# MCU.net
KiCad netlist of a schematic drawn in Altium Designer
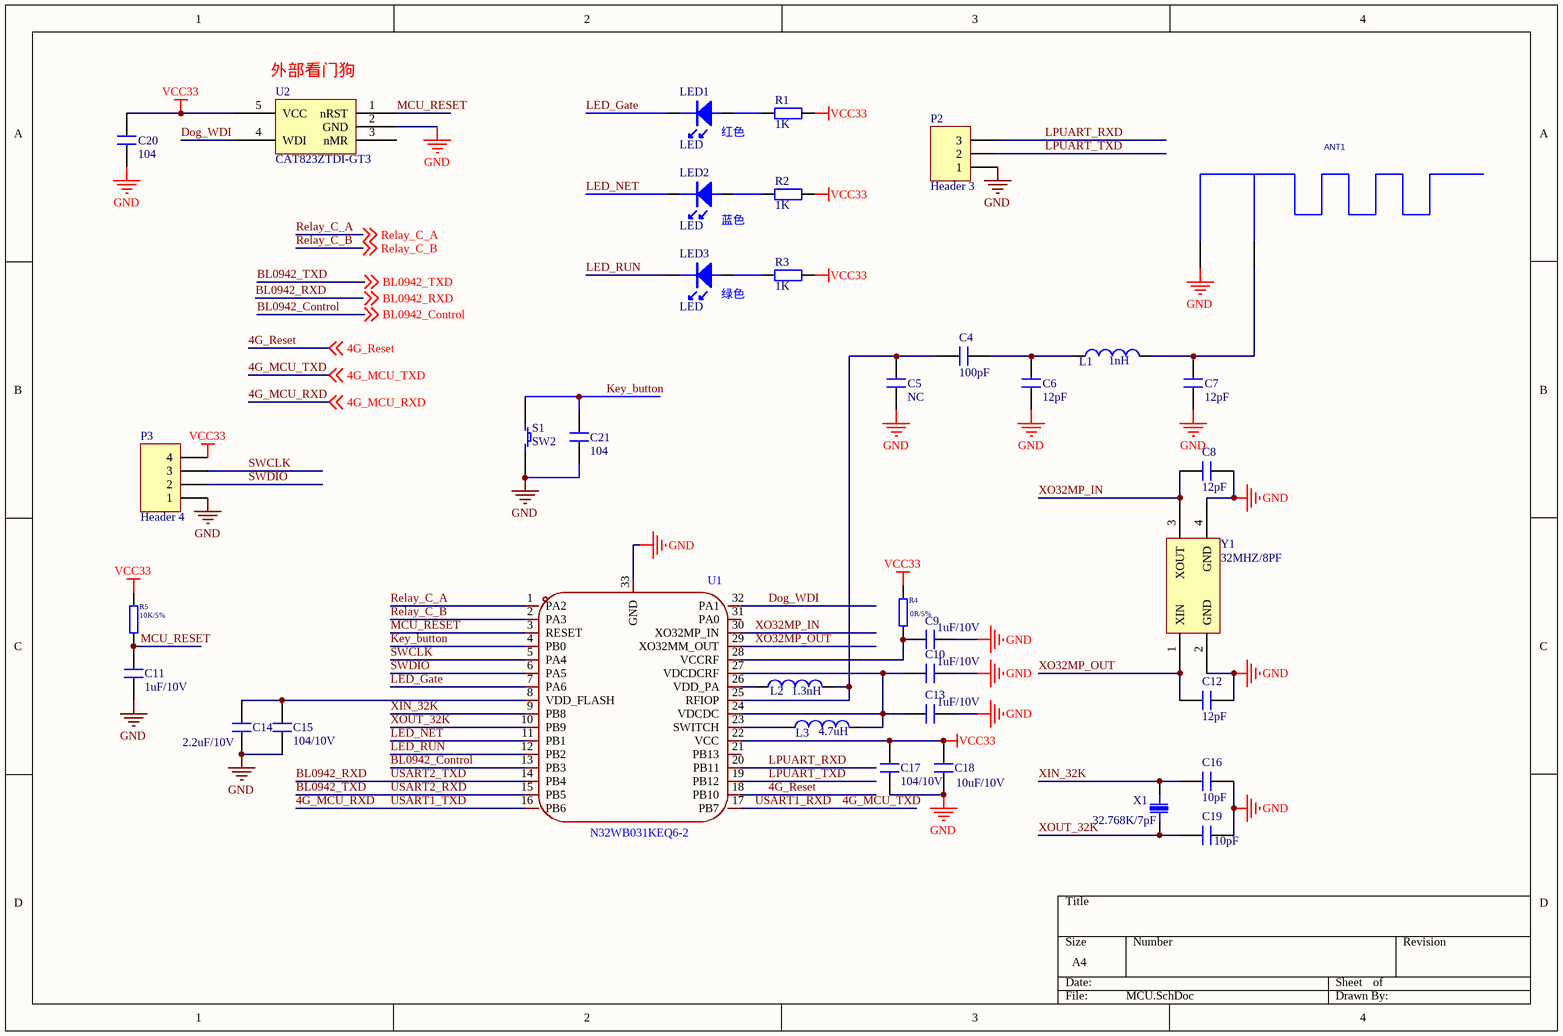
[diagram p0: MCU.SchDoc]

(export (version "E")
  (design (tool "Eeschema 10.0.6"))
  (components
    (comp (ref "ANT1")
      (value "ANT_2.4G")
      (footprint "ANTENNA_IIFA_BLE_MIRROR")
      (description "连接器，4PIN，2.0mm脚间距离，防呆直插件")
      (libsource (lib "*") (part "ANT_2.4G"))
    )
    (comp (ref "C4") (value "100pF") (footprint "0603R") (libsource (lib "ES_Schematic") (part "CAP_1")))
    (comp (ref "C5") (value "NC") (footprint "0603R") (libsource (lib "ES_Schematic") (part "CAP_1")))
    (comp (ref "C6") (value "12pF") (footprint "0603R") (libsource (lib "ES_Schematic") (part "CAP_1")))
    (comp (ref "C7") (value "12pF") (footprint "0603R") (libsource (lib "ES_Schematic") (part "CAP_1")))
    (comp (ref "C8") (value "12pF") (footprint "0603r") (libsource (lib "ES_Schematic") (part "CAP")))
    (comp (ref "C9") (value "1uF/10V") (footprint "0603R") (libsource (lib "ES_Schematic") (part "CAP_1")))
    (comp (ref "C10") (value "1uF/10V") (footprint "0603R") (libsource (lib "ES_Schematic") (part "CAP_1")))
    (comp (ref "C11") (value "1uF/10V") (footprint "0603R") (libsource (lib "ES_Schematic") (part "CAP_1")))
    (comp (ref "C12") (value "12pF") (footprint "0603r") (libsource (lib "ES_Schematic") (part "CAP")))
    (comp (ref "C13") (value "1uF/10V") (footprint "0603R") (libsource (lib "ES_Schematic") (part "CAP_1")))
    (comp (ref "C14") (value "2.2uF/10V") (footprint "0603R") (libsource (lib "ES_Schematic") (part "CAP_1")))
    (comp (ref "C15") (value "104/10V") (footprint "0603R") (libsource (lib "ES_Schematic") (part "CAP_1")))
    (comp (ref "C16") (value "10pF") (footprint "0603r") (libsource (lib "ES_Schematic") (part "CAP")))
    (comp (ref "C17") (value "104/10V") (footprint "0603R") (libsource (lib "ES_Schematic") (part "CAP_1")))
    (comp (ref "C18") (value "10uF/10V") (footprint "0603R") (libsource (lib "ES_Schematic") (part "CAP_1")))
    (comp (ref "C19") (value "10pF") (footprint "0603r") (libsource (lib "ES_Schematic") (part "CAP")))
    (comp (ref "C20") (value "104") (footprint "0603R") (libsource (lib "ES_Schematic") (part "CAP")))
    (comp (ref "C21") (value "104") (footprint "0603R") (libsource (lib "ES_Schematic") (part "CAP")))
    (comp (ref "L1")
      (value "1nH")
      (footprint "贴片电感5020")
      (description "Inductor")
      (fields (field (name "PUBLISHER") "Altium Limited"))
      (libsource (lib "Miscellaneous Devices") (part "Inductor"))
    )
    (comp (ref "L2")
      (value "1.3nH")
      (footprint "贴片电感5020")
      (description "Inductor")
      (fields (field (name "PUBLISHER") "Altium Limited"))
      (libsource (lib "Miscellaneous Devices") (part "Inductor"))
    )
    (comp (ref "L3")
      (value "4.7uH")
      (footprint "贴片电感5020")
      (description "Inductor")
      (fields (field (name "PUBLISHER") "Altium Limited"))
      (libsource (lib "Miscellaneous Devices") (part "Inductor"))
    )
    (comp (ref "LED1") (value "LED") (footprint "LED0805") (libsource (lib "ES_Schematic") (part "LED")))
    (comp (ref "LED2") (value "LED") (footprint "LED0805") (libsource (lib "ES_Schematic") (part "LED")))
    (comp (ref "LED3") (value "LED") (footprint "LED0805") (libsource (lib "ES_Schematic") (part "LED")))
    (comp (ref "P2")
      (value "Header 3")
      (footprint "HDR1X3")
      (description "Header, 3-Pin")
      (fields (field (name "PUBLISHER") "Altium Limited"))
      (libsource (lib "Miscellaneous Connectors") (part "Header 3"))
    )
    (comp (ref "P3")
      (value "Header 4")
      (footprint "HDR1X4")
      (description "Header, 4-Pin")
      (fields (field (name "PUBLISHER") "Altium Limited"))
      (libsource (lib "Miscellaneous Connectors") (part "Header 4"))
    )
    (comp (ref "R1")
      (value "1K")
      (footprint "0603R")
      (fields (field (name "Comment") "Res2") (field (name "PUBLISHER") "Altium Limited"))
      (libsource (lib "Miscellaneous Devices") (part "Res2"))
    )
    (comp (ref "R2")
      (value "1K")
      (footprint "0603R")
      (fields (field (name "Comment") "Res2") (field (name "PUBLISHER") "Altium Limited"))
      (libsource (lib "Miscellaneous Devices") (part "Res2"))
    )
    (comp (ref "R3")
      (value "1K")
      (footprint "0603R")
      (fields (field (name "Comment") "Res2") (field (name "PUBLISHER") "Altium Limited"))
      (libsource (lib "Miscellaneous Devices") (part "Res2"))
    )
    (comp (ref "R4") (value "0R/5%") (footprint "0603R") (libsource (lib "ES_Schematic") (part "RES")))
    (comp (ref "R5") (value "10K/5%") (footprint "0603R") (libsource (lib "ES_Schematic") (part "RES")))
    (comp (ref "S1")
      (value "SW2")
      (footprint "4.5*4.5贴片4脚独立按键")
      (libsource (lib "ES_Schematic") (part "SW2"))
    )
    (comp (ref "U1")
      (value "N32WB031KEQ6-2")
      (footprint "QFN-32_L4.0-W4.0-P0.40-TL-EP2.8")
      (fields (field (name "MANUFACTURER") "Nations(国民技术)"))
      (libsource (lib "altium-import") (part "root_0_N32WB031KEQ6-2_"))
    )
    (comp (ref "U2")
      (value "CAT823ZTDI-GT3")
      (footprint "SOT-23-5")
      (libsource (lib "ES_Schematic") (part "CAT823"))
    )
    (comp (ref "X1") (value "32.768K/7pF") (footprint "Y3215") (libsource (lib "ES_Schematic") (part "XTAL")))
    (comp (ref "Y1") (value "32MHZ/8PF") (footprint "3225") (libsource (lib "others") (part "12MHz无源")))
  )
  (nets
    (net (code "1") (name "/Dog_WDI") (class "Default")
      (node (ref "U1") (pin "32") (pinfunction "PA1_32") (pintype "passive"))
      (node (ref "U2") (pin "4") (pinfunction "WDI_4") (pintype "passive"))
    )
    (net (code "2") (name "/Key_button") (class "Default")
      (node (ref "C21") (pin "1") (pinfunction "1_1") (pintype "passive"))
      (node (ref "S1") (pin "1") (pinfunction "1_1") (pintype "passive"))
      (node (ref "U1") (pin "4") (pinfunction "PB0_4") (pintype "passive"))
    )
    (net (code "3") (name "/LED_Gate") (class "Default")
      (node (ref "LED1") (pin "2") (pinfunction "2_2") (pintype "passive"))
      (node (ref "U1") (pin "7") (pinfunction "PA6_7") (pintype "passive"))
    )
    (net (code "4") (name "/LED_NET") (class "Default")
      (node (ref "LED2") (pin "2") (pinfunction "2_2") (pintype "passive"))
      (node (ref "U1") (pin "11") (pinfunction "PB1_11") (pintype "passive"))
    )
    (net (code "5") (name "/LED_RUN") (class "Default")
      (node (ref "LED3") (pin "2") (pinfunction "2_2") (pintype "passive"))
      (node (ref "U1") (pin "12") (pinfunction "PB2_12") (pintype "passive"))
    )
    (net (code "6") (name "/LPUART_RXD") (class "Default")
      (node (ref "P2") (pin "3") (pinfunction "3_3") (pintype "passive"))
      (node (ref "U1") (pin "20") (pinfunction "PB11_20") (pintype "passive"))
    )
    (net (code "7") (name "/LPUART_TXD") (class "Default")
      (node (ref "P2") (pin "2") (pinfunction "2_2") (pintype "passive"))
      (node (ref "U1") (pin "19") (pinfunction "PB12_19") (pintype "passive"))
    )
    (net (code "8") (name "/MCU_RESET") (class "Default")
      (node (ref "C11") (pin "2") (pinfunction "2_2") (pintype "passive"))
      (node (ref "R5") (pin "2") (pinfunction "2_2") (pintype "passive"))
      (node (ref "U1") (pin "3") (pinfunction "RESET_3") (pintype "passive"))
      (node (ref "U2") (pin "1") (pinfunction "nRST_1") (pintype "passive"))
    )
    (net (code "9") (name "/SWCLK") (class "Default")
      (node (ref "P3") (pin "3") (pinfunction "3_3") (pintype "passive"))
      (node (ref "U1") (pin "5") (pinfunction "PA4_5") (pintype "passive"))
    )
    (net (code "10") (name "/SWDIO") (class "Default")
      (node (ref "P3") (pin "2") (pinfunction "2_2") (pintype "passive"))
      (node (ref "U1") (pin "6") (pinfunction "PA5_6") (pintype "passive"))
    )
    (net (code "11") (name "/XIN_32K") (class "Default")
      (node (ref "C16") (pin "1") (pinfunction "1_1") (pintype "passive"))
      (node (ref "U1") (pin "9") (pinfunction "PB8_9") (pintype "passive"))
      (node (ref "X1") (pin "2") (pinfunction "2_2") (pintype "passive"))
    )
    (net (code "12") (name "/XO32MP_IN") (class "Default")
      (node (ref "C8") (pin "2") (pinfunction "2_2") (pintype "passive"))
      (node (ref "U1") (pin "30") (pinfunction "XO32MP_IN_30") (pintype "passive"))
      (node (ref "Y1") (pin "3") (pinfunction "XOUT_3") (pintype "passive"))
    )
    (net (code "13") (name "/XO32MP_OUT") (class "Default")
      (node (ref "C12") (pin "2") (pinfunction "2_2") (pintype "passive"))
      (node (ref "U1") (pin "29") (pinfunction "XO32MM_OUT_29") (pintype "passive"))
      (node (ref "Y1") (pin "1") (pinfunction "XIN_1") (pintype "passive"))
    )
    (net (code "14") (name "/XOUT_32K") (class "Default")
      (node (ref "C19") (pin "2") (pinfunction "2_2") (pintype "passive"))
      (node (ref "U1") (pin "10") (pinfunction "PB9_10") (pintype "passive"))
      (node (ref "X1") (pin "1") (pinfunction "1_1") (pintype "passive"))
    )
    (net (code "15") (name "4G_MCU_RXD") (class "Default")
      (node (ref "U1") (pin "16") (pinfunction "PB6_16") (pintype "passive"))
    )
    (net (code "16") (name "4G_MCU_TXD") (class "Default")
      (node (ref "U1") (pin "17") (pinfunction "PB7_17") (pintype "passive"))
    )
    (net (code "17") (name "4G_Reset") (class "Default")
      (node (ref "U1") (pin "18") (pinfunction "PB10_18") (pintype "passive"))
    )
    (net (code "18") (name "BL0942_Control") (class "Default")
      (node (ref "U1") (pin "13") (pinfunction "PB3_13") (pintype "passive"))
    )
    (net (code "19") (name "BL0942_RXD") (class "Default")
      (node (ref "U1") (pin "14") (pinfunction "PB4_14") (pintype "passive"))
    )
    (net (code "20") (name "BL0942_TXD") (class "Default")
      (node (ref "U1") (pin "15") (pinfunction "PB5_15") (pintype "passive"))
    )
    (net (code "21") (name "GND") (class "Default")
      (node (ref "ANT1") (pin "2") (pinfunction "2_2") (pintype "passive"))
      (node (ref "C10") (pin "1") (pinfunction "1_1") (pintype "passive"))
      (node (ref "C11") (pin "1") (pinfunction "1_1") (pintype "passive"))
      (node (ref "C12") (pin "1") (pinfunction "1_1") (pintype "passive"))
      (node (ref "C13") (pin "1") (pinfunction "1_1") (pintype "passive"))
      (node (ref "C14") (pin "1") (pinfunction "1_1") (pintype "passive"))
      (node (ref "C15") (pin "1") (pinfunction "1_1") (pintype "passive"))
      (node (ref "C16") (pin "2") (pinfunction "2_2") (pintype "passive"))
      (node (ref "C17") (pin "1") (pinfunction "1_1") (pintype "passive"))
      (node (ref "C18") (pin "1") (pinfunction "1_1") (pintype "passive"))
      (node (ref "C19") (pin "1") (pinfunction "1_1") (pintype "passive"))
      (node (ref "C20") (pin "1") (pinfunction "1_1") (pintype "passive"))
      (node (ref "C21") (pin "2") (pinfunction "2_2") (pintype "passive"))
      (node (ref "C5") (pin "2") (pinfunction "2_2") (pintype "passive"))
      (node (ref "C6") (pin "1") (pinfunction "1_1") (pintype "passive"))
      (node (ref "C7") (pin "1") (pinfunction "1_1") (pintype "passive"))
      (node (ref "C8") (pin "1") (pinfunction "1_1") (pintype "passive"))
      (node (ref "C9") (pin "1") (pinfunction "1_1") (pintype "passive"))
      (node (ref "P2") (pin "1") (pinfunction "1_1") (pintype "passive"))
      (node (ref "P3") (pin "1") (pinfunction "1_1") (pintype "passive"))
      (node (ref "S1") (pin "2") (pinfunction "2_2") (pintype "passive"))
      (node (ref "U1") (pin "33") (pinfunction "GND_33") (pintype "passive"))
      (node (ref "U2") (pin "2") (pinfunction "GND_2") (pintype "passive"))
      (node (ref "Y1") (pin "2") (pinfunction "GND_2") (pintype "passive"))
      (node (ref "Y1") (pin "4") (pinfunction "GND_4") (pintype "passive"))
    )
    (net (code "22") (name "Net-(ANT1-Pad1)") (class "Default")
      (node (ref "ANT1") (pin "1") (pinfunction "1_1") (pintype "passive"))
      (node (ref "C7") (pin "2") (pinfunction "2_2") (pintype "passive"))
      (node (ref "L1") (pin "2") (pinfunction "2_2") (pintype "passive"))
    )
    (net (code "23") (name "Net-(C4-Pad2)") (class "Default")
      (node (ref "C4") (pin "2") (pinfunction "2_2") (pintype "passive"))
      (node (ref "C6") (pin "2") (pinfunction "2_2") (pintype "passive"))
      (node (ref "L1") (pin "1") (pinfunction "1_1") (pintype "passive"))
    )
    (net (code "24") (name "Net-(LED1-Pad1)") (class "Default")
      (node (ref "LED1") (pin "1") (pinfunction "1_1") (pintype "passive"))
      (node (ref "R1") (pin "2") (pinfunction "2_2") (pintype "passive"))
    )
    (net (code "25") (name "Net-(LED2-Pad1)") (class "Default")
      (node (ref "LED2") (pin "1") (pinfunction "1_1") (pintype "passive"))
      (node (ref "R2") (pin "2") (pinfunction "2_2") (pintype "passive"))
    )
    (net (code "26") (name "Net-(LED3-Pad1)") (class "Default")
      (node (ref "LED3") (pin "1") (pinfunction "1_1") (pintype "passive"))
      (node (ref "R3") (pin "2") (pinfunction "2_2") (pintype "passive"))
    )
    (net (code "27") (name "Net-(U1-RFIOP)") (class "Default")
      (node (ref "C4") (pin "1") (pinfunction "1_1") (pintype "passive"))
      (node (ref "C5") (pin "1") (pinfunction "1_1") (pintype "passive"))
      (node (ref "L2") (pin "2") (pinfunction "2_2") (pintype "passive"))
      (node (ref "U1") (pin "25") (pinfunction "RFIOP_25") (pintype "passive"))
    )
    (net (code "28") (name "Net-(U1-SWITCH)") (class "Default")
      (node (ref "L3") (pin "1") (pinfunction "1_1") (pintype "passive"))
      (node (ref "U1") (pin "23") (pinfunction "SWITCH_23") (pintype "passive"))
    )
    (net (code "29") (name "Net-(U1-VCCRF)") (class "Default")
      (node (ref "C9") (pin "2") (pinfunction "2_2") (pintype "passive"))
      (node (ref "R4") (pin "2") (pinfunction "2_2") (pintype "passive"))
      (node (ref "U1") (pin "28") (pinfunction "VCCRF_28") (pintype "passive"))
    )
    (net (code "30") (name "Net-(U1-VDCDC)") (class "Default")
      (node (ref "C10") (pin "2") (pinfunction "2_2") (pintype "passive"))
      (node (ref "C13") (pin "2") (pinfunction "2_2") (pintype "passive"))
      (node (ref "L3") (pin "2") (pinfunction "2_2") (pintype "passive"))
      (node (ref "U1") (pin "24") (pinfunction "VDCDC_24") (pintype "passive"))
      (node (ref "U1") (pin "27") (pinfunction "VDCDCRF_27") (pintype "passive"))
    )
    (net (code "31") (name "Net-(U1-VDD_FLASH)") (class "Default")
      (node (ref "C14") (pin "2") (pinfunction "2_2") (pintype "passive"))
      (node (ref "C15") (pin "2") (pinfunction "2_2") (pintype "passive"))
      (node (ref "U1") (pin "8") (pinfunction "VDD_FLASH_8") (pintype "passive"))
    )
    (net (code "32") (name "Net-(U1-VDD_PA)") (class "Default")
      (node (ref "L2") (pin "1") (pinfunction "1_1") (pintype "passive"))
      (node (ref "U1") (pin "26") (pinfunction "VDD_PA_26") (pintype "passive"))
    )
    (net (code "33") (name "Relay_C_A") (class "Default")
      (node (ref "U1") (pin "1") (pinfunction "PA2_1") (pintype "passive"))
    )
    (net (code "34") (name "Relay_C_B") (class "Default")
      (node (ref "U1") (pin "2") (pinfunction "PA3_2") (pintype "passive"))
    )
    (net (code "35") (name "VCC33") (class "Default")
      (node (ref "C17") (pin "2") (pinfunction "2_2") (pintype "passive"))
      (node (ref "C18") (pin "2") (pinfunction "2_2") (pintype "passive"))
      (node (ref "C20") (pin "2") (pinfunction "2_2") (pintype "passive"))
      (node (ref "P3") (pin "4") (pinfunction "4_4") (pintype "passive"))
      (node (ref "R1") (pin "1") (pinfunction "1_1") (pintype "passive"))
      (node (ref "R2") (pin "1") (pinfunction "1_1") (pintype "passive"))
      (node (ref "R3") (pin "1") (pinfunction "1_1") (pintype "passive"))
      (node (ref "R4") (pin "1") (pinfunction "1_1") (pintype "passive"))
      (node (ref "R5") (pin "1") (pinfunction "1_1") (pintype "passive"))
      (node (ref "U1") (pin "22") (pinfunction "VCC_22") (pintype "passive"))
      (node (ref "U2") (pin "5") (pinfunction "VCC_5") (pintype "passive"))
    )
    (net (code "36") (name "unconnected-(U1-PA0-Pad31)") (class "Default")
      (node (ref "U1") (pin "31") (pinfunction "PA0_31") (pintype "passive"))
    )
    (net (code "37") (name "unconnected-(U1-PB13-Pad21)") (class "Default")
      (node (ref "U1") (pin "21") (pinfunction "PB13_21") (pintype "passive"))
    )
    (net (code "38") (name "unconnected-(U2-nMR-Pad3)") (class "Default")
      (node (ref "U2") (pin "3") (pinfunction "nMR_3") (pintype "passive"))
    )
  )
)
